# 7_TSAL_Red.net
KiCad netlist of a schematic drawn in Altium Designer
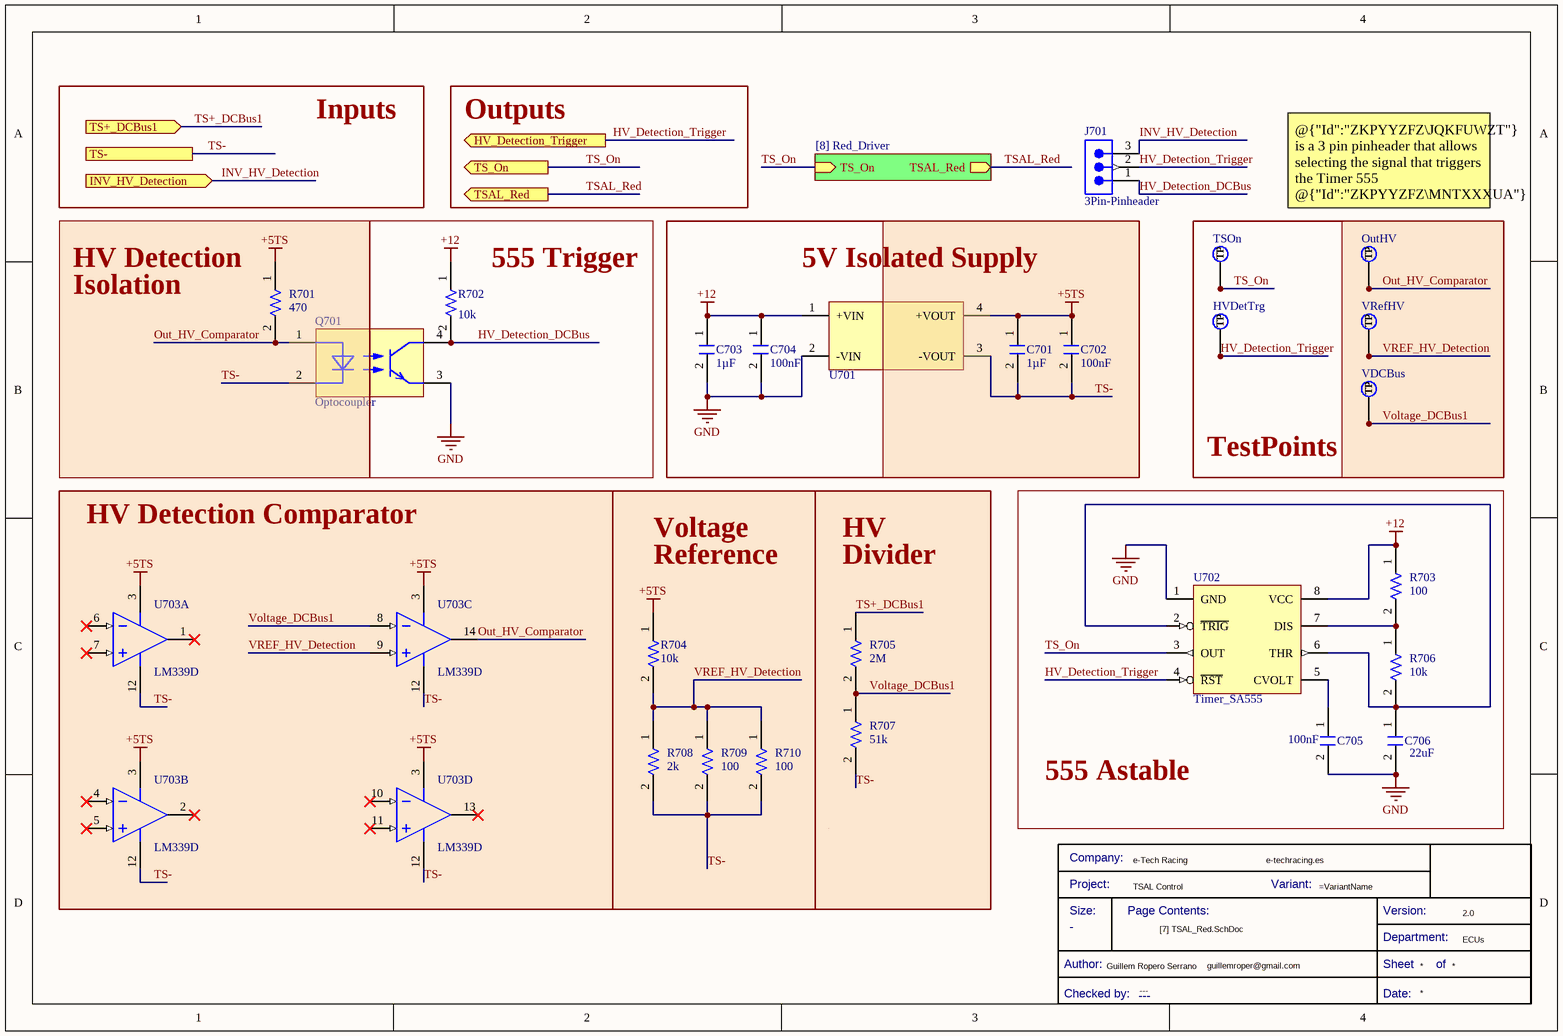
[diagram p0: [7] TSAL_Red.SchDoc]

(export (version "E")
  (design (tool "Eeschema 10.0.6"))
  (components
    (comp (ref "C701")
      (value "1µF")
      (footprint "C0805FNPC-R")
      (fields
        (field (name "TOLERANCE") "10%")
        (field (name "Comment") "C1u-50V-0805FNPC-X7R")
        (field (name ".CREATOR") "GP")
      )
      (libsource (lib "EMEA- E-Tech Racing- I'Escola d'Enginyeria de Barcelona Est") (part "C1u"))
    )
    (comp (ref "C702")
      (value "C100n-16V-0805")
      (footprint "WCAP-CSGP_0805_L2W1.25H0.8_Reflow")
      (fields (field (name "CAPACITANCE") "100nF"))
      (libsource (lib "EMEA- E-Tech Racing- I'Escola d'Enginyeria de Barcelona Est") (part "C100p-50V-0805FNPC-C0G/NP0"))
    )
    (comp (ref "C703")
      (value "1µF")
      (footprint "C0805FNPC-R")
      (fields
        (field (name "TOLERANCE") "10%")
        (field (name "Comment") "C1u-50V-0805FNPC-X7R")
        (field (name ".CREATOR") "GP")
      )
      (libsource (lib "EMEA- E-Tech Racing- I'Escola d'Enginyeria de Barcelona Est") (part "C1u"))
    )
    (comp (ref "C704")
      (value "C100n-16V-0805")
      (footprint "WCAP-CSGP_0805_L2W1.25H0.8_Reflow")
      (fields (field (name "CAPACITANCE") "100nF"))
      (libsource (lib "EMEA- E-Tech Racing- I'Escola d'Enginyeria de Barcelona Est") (part "C100p-50V-0805FNPC-C0G/NP0"))
    )
    (comp (ref "C705")
      (value "100nF")
      (footprint "WCAP-CSGP_0805_L2W1.25H0.8_Reflow")
      (fields (field (name "Comment") "C100n-16V-0805"))
      (libsource (lib "EMEA- E-Tech Racing- I'Escola d'Enginyeria de Barcelona Est") (part "C100p-50V-0805FNPC-C0G/NP0"))
    )
    (comp (ref "C706")
      (value "22uF")
      (footprint "WCAP-CSGP_0805_L2W1.25H0.8_Reflow")
      (description "885012107019")
      (fields (field (name "Comment") "C22u-25V-0805"))
      (libsource (lib "EMEA- E-Tech Racing- I'Escola d'Enginyeria de Barcelona Est") (part "C100p-50V-0805FNPC-C0G/NP0"))
    )
    (comp (ref "HVDetTrg")
      (value "TestPoint")
      (footprint "TestPoint")
      (description "Test Point 1x1 mm")
      (fields (field (name ".SCHCHECK") "GP") (field (name ".CREATOR") "GP") (field (name ".PCBCHECK") "GP"))
      (libsource (lib "EMEA- E-Tech Racing- I'Escola d'Enginyeria de Barcelona Est") (part "TestPoint"))
    )
    (comp (ref "J701")
      (value "3Pin-Pinheader")
      (footprint "61300311121")
      (libsource (lib "EMEA- E-Tech Racing- I'Escola d'Enginyeria de Barcelona Est") (part "Header_Male_1R_03P"))
    )
    (comp (ref "OutHV")
      (value "TestPoint")
      (footprint "TestPoint")
      (description "Test Point 1x1 mm")
      (fields (field (name ".SCHCHECK") "GP") (field (name ".CREATOR") "GP") (field (name ".PCBCHECK") "GP"))
      (libsource (lib "EMEA- E-Tech Racing- I'Escola d'Enginyeria de Barcelona Est") (part "TestPoint"))
    )
    (comp (ref "Q701")
      (value "Optocoupler")
      (footprint "WL-OCPT_LSOP4")
      (description "Transistor Output Optocoupler. S/N: 140100146000")
      (libsource (lib "EMEA- E-Tech Racing- I'Escola d'Enginyeria de Barcelona Est") (part "Optocoupler Phototransistor_DC_1 Channel"))
    )
    (comp (ref "R701")
      (value "470")
      (footprint "R0805FTK")
      (description "Res Thick Film 0805 470 Ohm 1% 1/8W ±100ppm/°C Molded SMD SMD Paper Tape on Plastic Reel")
      (fields
        (field (name "TOLERANCE") "1%")
        (field (name "Comment") "R470-0805FTK")
        (field (name ".CREATOR") "DR")
      )
      (libsource (lib "EMEA- E-Tech Racing- I'Escola d'Enginyeria de Barcelona Est") (part "CRCW08055K30FKTA"))
    )
    (comp (ref "R702")
      (value "10k")
      (footprint "R0805FTK")
      (fields
        (field (name "TOLERANCE") "5%")
        (field (name "Comment") "R10k-0805FTK")
        (field (name ".CREATOR") "DR")
      )
      (libsource (lib "EMEA- E-Tech Racing- I'Escola d'Enginyeria de Barcelona Est") (part "R"))
    )
    (comp (ref "R703")
      (value "100")
      (footprint "R0805FTK")
      (description "Res Thick Film 0805 100 Ohm 1% 1/8W ±100ppm/°C Molded SMD SMD Paper Tape on Plastic Reel")
      (fields
        (field (name "TOLERANCE") "1%")
        (field (name "Comment") "R100-0805FTK")
        (field (name ".CREATOR") "DR")
      )
      (libsource (lib "EMEA- E-Tech Racing- I'Escola d'Enginyeria de Barcelona Est") (part "CRCW08055K30FKTA"))
    )
    (comp (ref "R704")
      (value "R10k_0805_0.25W")
      (footprint "0805")
      (description "Resistor, 10K, 0.25W, Thick Film, 0805 Rohs Compliant: Yes")
      (fields (field (name "RESISTANCE") "10k"))
      (libsource (lib "EMEA- E-Tech Racing- I'Escola d'Enginyeria de Barcelona Est") (part "CRCW08055K30FKTA"))
    )
    (comp (ref "R705")
      (value "R2M-2512FTK")
      (footprint "R2512FTK")
      (description "Current Sense Resistors - SMD 3watts .002ohms 1%")
      (fields
        (field (name "RESISTANCE") "2M")
        (field (name "MANUFACTURER") "Vishay Dale")
        (field (name "TOLERANCE") "1%")
      )
      (libsource (lib "EMEA- E-Tech Racing- I'Escola d'Enginyeria de Barcelona Est") (part "CRCW08055K30FKTA"))
    )
    (comp (ref "R706")
      (value "10k")
      (footprint "R0805FTK")
      (fields
        (field (name "TOLERANCE") "5%")
        (field (name "Comment") "R10k-0805FTK")
        (field (name ".CREATOR") "DR")
      )
      (libsource (lib "EMEA- E-Tech Racing- I'Escola d'Enginyeria de Barcelona Est") (part "R"))
    )
    (comp (ref "R707")
      (value "51k")
      (footprint "0805")
      (fields
        (field (name "POWER") "125mW")
        (field (name "TOLERANCE") "1%")
        (field (name "Comment") "R51k_0805")
      )
      (libsource (lib "EMEA- E-Tech Racing- I'Escola d'Enginyeria de Barcelona Est") (part "CRCW08055K30FKTA"))
    )
    (comp (ref "R708")
      (value "2k")
      (footprint "0805")
      (fields
        (field (name "POWER") "500mW")
        (field (name "MANUFACTURER") "Vishay")
        (field (name "TOLERANCE") "1%")
      )
      (libsource (lib "EMEA- E-Tech Racing- I'Escola d'Enginyeria de Barcelona Est") (part "R9.09K-1206FTK"))
    )
    (comp (ref "R709")
      (value "100")
      (footprint "R0805FTK")
      (description "Res Thick Film 0805 100 Ohm 1% 1/8W ±100ppm/°C Molded SMD SMD Paper Tape on Plastic Reel")
      (fields
        (field (name "TOLERANCE") "1%")
        (field (name "Comment") "R100-0805FTK")
        (field (name ".CREATOR") "DR")
      )
      (libsource (lib "EMEA- E-Tech Racing- I'Escola d'Enginyeria de Barcelona Est") (part "CRCW08055K30FKTA"))
    )
    (comp (ref "R710")
      (value "100")
      (footprint "R0805FTK")
      (description "Res Thick Film 0805 100 Ohm 1% 1/8W ±100ppm/°C Molded SMD SMD Paper Tape on Plastic Reel")
      (fields
        (field (name "TOLERANCE") "1%")
        (field (name "Comment") "R100-0805FTK")
        (field (name ".CREATOR") "DR")
      )
      (libsource (lib "EMEA- E-Tech Racing- I'Escola d'Enginyeria de Barcelona Est") (part "CRCW08055K30FKTA"))
    )
    (comp (ref "TSOn")
      (value "TestPoint")
      (footprint "TestPoint")
      (description "Test Point 1x1 mm")
      (fields (field (name ".SCHCHECK") "GP") (field (name ".CREATOR") "GP") (field (name ".PCBCHECK") "GP"))
      (libsource (lib "EMEA- E-Tech Racing- I'Escola d'Enginyeria de Barcelona Est") (part "TestPoint"))
    )
    (comp (ref "U701")
      (value "DCDC_ISO_12VIN_5VOUT")
      (footprint "WPME-FISM_SIP-7_L19.65W7.05H10.16")
      (description "WPME-FISM Fixed Isolated SIP/SMT Module")
      (libsource (lib "EMEA- E-Tech Racing- I'Escola d'Enginyeria de Barcelona Est") (part "SIP-7 - WPME-FISM"))
    )
    (comp (ref "U702")
      (value "Timer_SA555")
      (footprint "Timer_SA555")
      (description "Precision timer for -55 to 85C operation 8-SOIC -40 to 85")
      (fields
        (field (name "MANUFACTURER PART NUMBER") "SA555D")
        (field (name "MANUFACTURER") "Texas Instruments")
        (field (name ".CREATOR") "DO")
      )
      (libsource (lib "EMEA- E-Tech Racing- I'Escola d'Enginyeria de Barcelona Est") (part "Timer_SA555"))
    )
    (comp (ref "U703")
      (value "LM339D")
      (footprint "D0014A_N")
      (description "Comparator, 4 Func, 5000uV Offset-Max, 300ns Response Time, BIPolar, PDSO14")
      (libsource (lib "EMEA- E-Tech Racing- I'Escola d'Enginyeria de Barcelona Est") (part "TI-LMXXXX14"))
    )
    (comp (ref "VDCBus")
      (value "TestPoint")
      (footprint "TestPoint")
      (description "Test Point 1x1 mm")
      (fields (field (name ".SCHCHECK") "GP") (field (name ".CREATOR") "GP") (field (name ".PCBCHECK") "GP"))
      (libsource (lib "EMEA- E-Tech Racing- I'Escola d'Enginyeria de Barcelona Est") (part "TestPoint"))
    )
    (comp (ref "VRefHV")
      (value "TestPoint")
      (footprint "TestPoint")
      (description "Test Point 1x1 mm")
      (fields (field (name ".SCHCHECK") "GP") (field (name ".CREATOR") "GP") (field (name ".PCBCHECK") "GP"))
      (libsource (lib "EMEA- E-Tech Racing- I'Escola d'Enginyeria de Barcelona Est") (part "TestPoint"))
    )
  )
  (nets
    (net (code "1") (name "+5TS") (class "Default")
      (node (ref "C701") (pin "1") (pinfunction "1_1") (pintype "passive"))
      (node (ref "C702") (pin "1") (pinfunction "1_1") (pintype "passive"))
      (node (ref "R701") (pin "1") (pinfunction "1_1") (pintype "passive"))
      (node (ref "R704") (pin "1") (pinfunction "1_1") (pintype "passive"))
      (node (ref "U701") (pin "4") (pinfunction "+VOUT_4") (pintype "passive"))
      (node (ref "U703") (pin "3") (pinfunction "VCC_3") (pintype "power_in"))
    )
    (net (code "2") (name "+12") (class "Default")
      (node (ref "C703") (pin "1") (pinfunction "1_1") (pintype "passive"))
      (node (ref "C704") (pin "1") (pinfunction "1_1") (pintype "passive"))
      (node (ref "R702") (pin "1") (pinfunction "1_1") (pintype "passive"))
      (node (ref "R703") (pin "1") (pinfunction "1_1") (pintype "passive"))
      (node (ref "U701") (pin "1") (pinfunction "+VIN_1") (pintype "passive"))
      (node (ref "U702") (pin "8") (pinfunction "VCC_8") (pintype "passive"))
    )
    (net (code "3") (name "/HV_Detection_DCBus") (class "Default")
      (node (ref "J701") (pin "1") (pinfunction "1_1") (pintype "passive"))
      (node (ref "Q701") (pin "4") (pinfunction "Collector_4") (pintype "passive"))
      (node (ref "R702") (pin "2") (pinfunction "2_2") (pintype "passive"))
    )
    (net (code "4") (name "/HV_Detection_Trigger") (class "Default")
      (node (ref "HVDetTrg") (pin "1") (pinfunction "TP_1") (pintype "passive"))
      (node (ref "J701") (pin "2") (pinfunction "2_2") (pintype "output"))
      (node (ref "U702") (pin "4") (pinfunction "~{RST}_4") (pintype "input"))
    )
    (net (code "5") (name "/INV_HV_Detection") (class "Default")
      (node (ref "J701") (pin "3") (pinfunction "3_3") (pintype "passive"))
    )
    (net (code "6") (name "/Out_HV_Comparator") (class "Default")
      (node (ref "OutHV") (pin "1") (pinfunction "TP_1") (pintype "passive"))
      (node (ref "Q701") (pin "1") (pinfunction "Anode_1") (pintype "passive"))
      (node (ref "R701") (pin "2") (pinfunction "2_2") (pintype "passive"))
      (node (ref "U703") (pin "14") (pinfunction "OUT3_14") (pintype "open_collector"))
    )
    (net (code "7") (name "/TS+_DCBus1") (class "Default")
      (node (ref "R705") (pin "1") (pinfunction "1_1") (pintype "passive"))
    )
    (net (code "8") (name "/TS-") (class "Default")
      (node (ref "C701") (pin "2") (pinfunction "2_2") (pintype "passive"))
      (node (ref "C702") (pin "2") (pinfunction "2_2") (pintype "passive"))
      (node (ref "Q701") (pin "2") (pinfunction "Cathode_2") (pintype "passive"))
      (node (ref "R707") (pin "2") (pinfunction "2_2") (pintype "passive"))
      (node (ref "R708") (pin "2") (pinfunction "2_2") (pintype "passive"))
      (node (ref "R709") (pin "2") (pinfunction "2_2") (pintype "passive"))
      (node (ref "R710") (pin "2") (pinfunction "2_2") (pintype "passive"))
      (node (ref "U701") (pin "3") (pinfunction "-VOUT_3") (pintype "passive"))
      (node (ref "U703") (pin "12") (pinfunction "GND_12") (pintype "power_in"))
    )
    (net (code "10") (name "/TS_On") (class "Default")
      (node (ref "TSOn") (pin "1") (pinfunction "TP_1") (pintype "passive"))
      (node (ref "U702") (pin "3") (pinfunction "OUT_3") (pintype "output"))
    )
    (net (code "11") (name "/VREF_HV_Detection") (class "Default")
      (node (ref "R704") (pin "2") (pinfunction "2_2") (pintype "passive"))
      (node (ref "R708") (pin "1") (pinfunction "1_1") (pintype "passive"))
      (node (ref "R709") (pin "1") (pinfunction "1_1") (pintype "passive"))
      (node (ref "R710") (pin "1") (pinfunction "1_1") (pintype "passive"))
      (node (ref "U703") (pin "9") (pinfunction "IN3+_9") (pintype "input"))
      (node (ref "VRefHV") (pin "1") (pinfunction "TP_1") (pintype "passive"))
    )
    (net (code "12") (name "/Voltage_DCBus1") (class "Default")
      (node (ref "R705") (pin "2") (pinfunction "2_2") (pintype "passive"))
      (node (ref "R707") (pin "1") (pinfunction "1_1") (pintype "passive"))
      (node (ref "U703") (pin "8") (pinfunction "IN3-_8") (pintype "input"))
      (node (ref "VDCBus") (pin "1") (pinfunction "TP_1") (pintype "passive"))
    )
    (net (code "13") (name "GND") (class "Default")
      (node (ref "C703") (pin "2") (pinfunction "2_2") (pintype "passive"))
      (node (ref "C704") (pin "2") (pinfunction "2_2") (pintype "passive"))
      (node (ref "C705") (pin "2") (pinfunction "2_2") (pintype "passive"))
      (node (ref "C706") (pin "2") (pinfunction "2_2") (pintype "passive"))
      (node (ref "Q701") (pin "3") (pinfunction "Emitter_3") (pintype "passive"))
      (node (ref "U701") (pin "2") (pinfunction "-VIN_2") (pintype "passive"))
      (node (ref "U702") (pin "1") (pinfunction "GND_1") (pintype "passive"))
    )
    (net (code "14") (name "Net-(U702-CVOLT)") (class "Default")
      (node (ref "C705") (pin "1") (pinfunction "1_1") (pintype "passive"))
      (node (ref "U702") (pin "5") (pinfunction "CVOLT_5") (pintype "passive"))
    )
    (net (code "15") (name "Net-(U702-DIS)") (class "Default")
      (node (ref "R703") (pin "2") (pinfunction "2_2") (pintype "passive"))
      (node (ref "R706") (pin "1") (pinfunction "1_1") (pintype "passive"))
      (node (ref "U702") (pin "7") (pinfunction "DIS_7") (pintype "passive"))
    )
    (net (code "16") (name "Net-(U702-THR)") (class "Default")
      (node (ref "C706") (pin "1") (pinfunction "1_1") (pintype "passive"))
      (node (ref "R706") (pin "2") (pinfunction "2_2") (pintype "passive"))
      (node (ref "U702") (pin "2") (pinfunction "~{TRIG}_2") (pintype "input"))
      (node (ref "U702") (pin "6") (pinfunction "THR_6") (pintype "output"))
    )
    (net (code "17") (name "unconnected-(U703A-IN1+-Pad7)") (class "Default")
      (node (ref "U703") (pin "7") (pinfunction "IN1+_7") (pintype "input+no_connect"))
    )
    (net (code "18") (name "unconnected-(U703A-IN1--Pad6)") (class "Default")
      (node (ref "U703") (pin "6") (pinfunction "IN1-_6") (pintype "input+no_connect"))
    )
    (net (code "19") (name "unconnected-(U703A-OUT1-Pad1)") (class "Default")
      (node (ref "U703") (pin "1") (pinfunction "OUT1_1") (pintype "open_collector+no_connect"))
    )
    (net (code "20") (name "unconnected-(U703B-IN2+-Pad5)") (class "Default")
      (node (ref "U703") (pin "5") (pinfunction "IN2+_5") (pintype "input+no_connect"))
    )
    (net (code "21") (name "unconnected-(U703B-IN2--Pad4)") (class "Default")
      (node (ref "U703") (pin "4") (pinfunction "IN2-_4") (pintype "input+no_connect"))
    )
    (net (code "22") (name "unconnected-(U703B-OUT2-Pad2)") (class "Default")
      (node (ref "U703") (pin "2") (pinfunction "OUT2_2") (pintype "open_collector+no_connect"))
    )
    (net (code "23") (name "unconnected-(U703D-IN4+-Pad11)") (class "Default")
      (node (ref "U703") (pin "11") (pinfunction "IN4+_11") (pintype "input+no_connect"))
    )
    (net (code "24") (name "unconnected-(U703D-IN4--Pad10)") (class "Default")
      (node (ref "U703") (pin "10") (pinfunction "IN4-_10") (pintype "input+no_connect"))
    )
    (net (code "25") (name "unconnected-(U703D-OUT4-Pad13)") (class "Default")
      (node (ref "U703") (pin "13") (pinfunction "OUT4_13") (pintype "open_collector+no_connect"))
    )
  )
)
